# untitled.net
KiCad netlist of a schematic drawn in EAGLE
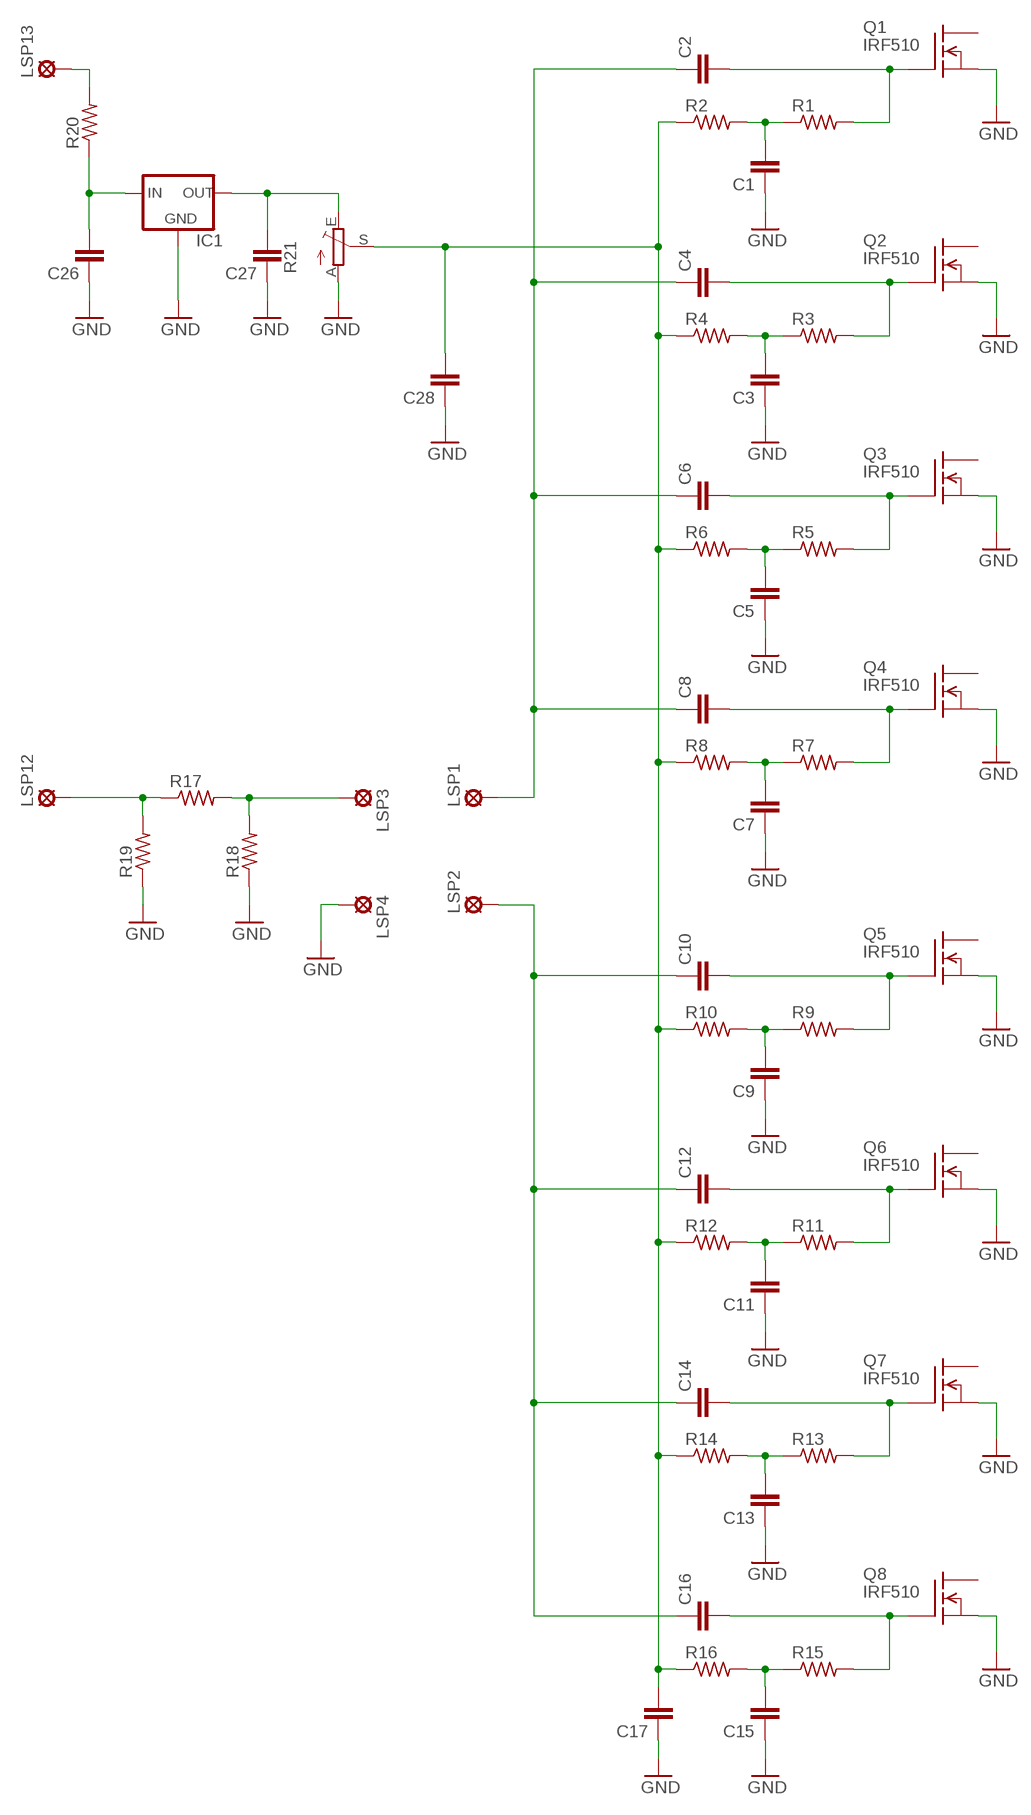
[diagram p0: schematic, sheet 1]

(export (version "E")
  (design (tool "Eeschema 10.0.6"))
  (components
    (comp (ref "C1")
      (value "C-EU075-032X103")
      (footprint "eagle-import:C075-032X103")
      (libsource (lib "eagle-import") (part "C-EU075-032X103"))
    )
    (comp (ref "C2")
      (value "C-EU075-032X103")
      (footprint "eagle-import:C075-032X103")
      (libsource (lib "eagle-import") (part "C-EU075-032X103"))
    )
    (comp (ref "C3")
      (value "C-EU075-032X103")
      (footprint "eagle-import:C075-032X103")
      (libsource (lib "eagle-import") (part "C-EU075-032X103"))
    )
    (comp (ref "C4")
      (value "C-EU075-032X103")
      (footprint "eagle-import:C075-032X103")
      (libsource (lib "eagle-import") (part "C-EU075-032X103"))
    )
    (comp (ref "C5")
      (value "C-EU075-032X103")
      (footprint "eagle-import:C075-032X103")
      (libsource (lib "eagle-import") (part "C-EU075-032X103"))
    )
    (comp (ref "C6")
      (value "C-EU075-032X103")
      (footprint "eagle-import:C075-032X103")
      (libsource (lib "eagle-import") (part "C-EU075-032X103"))
    )
    (comp (ref "C7")
      (value "C-EU075-032X103")
      (footprint "eagle-import:C075-032X103")
      (libsource (lib "eagle-import") (part "C-EU075-032X103"))
    )
    (comp (ref "C8")
      (value "C-EU075-032X103")
      (footprint "eagle-import:C075-032X103")
      (libsource (lib "eagle-import") (part "C-EU075-032X103"))
    )
    (comp (ref "C9")
      (value "C-EU075-032X103")
      (footprint "eagle-import:C075-032X103")
      (libsource (lib "eagle-import") (part "C-EU075-032X103"))
    )
    (comp (ref "C10")
      (value "C-EU075-032X103")
      (footprint "eagle-import:C075-032X103")
      (libsource (lib "eagle-import") (part "C-EU075-032X103"))
    )
    (comp (ref "C11")
      (value "C-EU075-032X103")
      (footprint "eagle-import:C075-032X103")
      (libsource (lib "eagle-import") (part "C-EU075-032X103"))
    )
    (comp (ref "C12")
      (value "C-EU075-032X103")
      (footprint "eagle-import:C075-032X103")
      (libsource (lib "eagle-import") (part "C-EU075-032X103"))
    )
    (comp (ref "C13")
      (value "C-EU075-032X103")
      (footprint "eagle-import:C075-032X103")
      (libsource (lib "eagle-import") (part "C-EU075-032X103"))
    )
    (comp (ref "C14")
      (value "C-EU075-032X103")
      (footprint "eagle-import:C075-032X103")
      (libsource (lib "eagle-import") (part "C-EU075-032X103"))
    )
    (comp (ref "C15")
      (value "C-EU075-032X103")
      (footprint "eagle-import:C075-032X103")
      (libsource (lib "eagle-import") (part "C-EU075-032X103"))
    )
    (comp (ref "C16")
      (value "C-EU075-032X103")
      (footprint "eagle-import:C075-032X103")
      (libsource (lib "eagle-import") (part "C-EU075-032X103"))
    )
    (comp (ref "C17")
      (value "C-EU075-032X103")
      (footprint "eagle-import:C075-032X103")
      (libsource (lib "eagle-import") (part "C-EU075-032X103"))
    )
    (comp (ref "C26")
      (value "C-EU075-032X103")
      (footprint "eagle-import:C075-032X103")
      (libsource (lib "eagle-import") (part "C-EU075-032X103"))
    )
    (comp (ref "C27")
      (value "C-EU075-032X103")
      (footprint "eagle-import:C075-032X103")
      (libsource (lib "eagle-import") (part "C-EU075-032X103"))
    )
    (comp (ref "C28")
      (value "C-EU075-032X103")
      (footprint "eagle-import:C075-032X103")
      (libsource (lib "eagle-import") (part "C-EU075-032X103"))
    )
    (comp (ref "IC1")
      (value "78XXS")
      (footprint "eagle-import:78XXS")
      (libsource (lib "eagle-import") (part "78XXS"))
    )
    (comp (ref "LSP1")
      (value "SE14")
      (footprint "eagle-import:SE14")
      (libsource (lib "eagle-import") (part "SE14"))
    )
    (comp (ref "LSP2")
      (value "SE14")
      (footprint "eagle-import:SE14")
      (libsource (lib "eagle-import") (part "SE14"))
    )
    (comp (ref "LSP3")
      (value "SE14")
      (footprint "eagle-import:SE14")
      (libsource (lib "eagle-import") (part "SE14"))
    )
    (comp (ref "LSP4")
      (value "SE14")
      (footprint "eagle-import:SE14")
      (libsource (lib "eagle-import") (part "SE14"))
    )
    (comp (ref "LSP12")
      (value "SE14")
      (footprint "eagle-import:SE14")
      (libsource (lib "eagle-import") (part "SE14"))
    )
    (comp (ref "LSP13")
      (value "SE14")
      (footprint "eagle-import:SE14")
      (libsource (lib "eagle-import") (part "SE14"))
    )
    (comp (ref "Q1")
      (value "IRF510")
      (footprint "eagle-import:TO220")
      (libsource (lib "eagle-import") (part "IRF510"))
    )
    (comp (ref "Q2")
      (value "IRF510")
      (footprint "eagle-import:TO220")
      (libsource (lib "eagle-import") (part "IRF510"))
    )
    (comp (ref "Q3")
      (value "IRF510")
      (footprint "eagle-import:TO220")
      (libsource (lib "eagle-import") (part "IRF510"))
    )
    (comp (ref "Q4")
      (value "IRF510")
      (footprint "eagle-import:TO220")
      (libsource (lib "eagle-import") (part "IRF510"))
    )
    (comp (ref "Q5")
      (value "IRF510")
      (footprint "eagle-import:TO220")
      (libsource (lib "eagle-import") (part "IRF510"))
    )
    (comp (ref "Q6")
      (value "IRF510")
      (footprint "eagle-import:TO220")
      (libsource (lib "eagle-import") (part "IRF510"))
    )
    (comp (ref "Q7")
      (value "IRF510")
      (footprint "eagle-import:TO220")
      (libsource (lib "eagle-import") (part "IRF510"))
    )
    (comp (ref "Q8")
      (value "IRF510")
      (footprint "eagle-import:TO220")
      (libsource (lib "eagle-import") (part "IRF510"))
    )
    (comp (ref "R1")
      (value "R-US_0309/12")
      (footprint "eagle-import:0309_12")
      (libsource (lib "eagle-import") (part "R-US_0309/12"))
    )
    (comp (ref "R2")
      (value "R-US_0309/12")
      (footprint "eagle-import:0309_12")
      (libsource (lib "eagle-import") (part "R-US_0309/12"))
    )
    (comp (ref "R3")
      (value "R-US_0309/12")
      (footprint "eagle-import:0309_12")
      (libsource (lib "eagle-import") (part "R-US_0309/12"))
    )
    (comp (ref "R4")
      (value "R-US_0309/12")
      (footprint "eagle-import:0309_12")
      (libsource (lib "eagle-import") (part "R-US_0309/12"))
    )
    (comp (ref "R5")
      (value "R-US_0309/12")
      (footprint "eagle-import:0309_12")
      (libsource (lib "eagle-import") (part "R-US_0309/12"))
    )
    (comp (ref "R6")
      (value "R-US_0309/12")
      (footprint "eagle-import:0309_12")
      (libsource (lib "eagle-import") (part "R-US_0309/12"))
    )
    (comp (ref "R7")
      (value "R-US_0309/12")
      (footprint "eagle-import:0309_12")
      (libsource (lib "eagle-import") (part "R-US_0309/12"))
    )
    (comp (ref "R8")
      (value "R-US_0309/12")
      (footprint "eagle-import:0309_12")
      (libsource (lib "eagle-import") (part "R-US_0309/12"))
    )
    (comp (ref "R9")
      (value "R-US_0309/12")
      (footprint "eagle-import:0309_12")
      (libsource (lib "eagle-import") (part "R-US_0309/12"))
    )
    (comp (ref "R10")
      (value "R-US_0309/12")
      (footprint "eagle-import:0309_12")
      (libsource (lib "eagle-import") (part "R-US_0309/12"))
    )
    (comp (ref "R11")
      (value "R-US_0309/12")
      (footprint "eagle-import:0309_12")
      (libsource (lib "eagle-import") (part "R-US_0309/12"))
    )
    (comp (ref "R12")
      (value "R-US_0309/12")
      (footprint "eagle-import:0309_12")
      (libsource (lib "eagle-import") (part "R-US_0309/12"))
    )
    (comp (ref "R13")
      (value "R-US_0309/12")
      (footprint "eagle-import:0309_12")
      (libsource (lib "eagle-import") (part "R-US_0309/12"))
    )
    (comp (ref "R14")
      (value "R-US_0309/12")
      (footprint "eagle-import:0309_12")
      (libsource (lib "eagle-import") (part "R-US_0309/12"))
    )
    (comp (ref "R15")
      (value "R-US_0309/12")
      (footprint "eagle-import:0309_12")
      (libsource (lib "eagle-import") (part "R-US_0309/12"))
    )
    (comp (ref "R16")
      (value "R-US_0309/12")
      (footprint "eagle-import:0309_12")
      (libsource (lib "eagle-import") (part "R-US_0309/12"))
    )
    (comp (ref "R17")
      (value "R-US_0309/12")
      (footprint "eagle-import:0309_12")
      (libsource (lib "eagle-import") (part "R-US_0309/12"))
    )
    (comp (ref "R18")
      (value "R-US_0309/12")
      (footprint "eagle-import:0309_12")
      (libsource (lib "eagle-import") (part "R-US_0309/12"))
    )
    (comp (ref "R19")
      (value "R-US_0309/12")
      (footprint "eagle-import:0309_12")
      (libsource (lib "eagle-import") (part "R-US_0309/12"))
    )
    (comp (ref "R20")
      (value "R-US_0309/12")
      (footprint "eagle-import:0309_12")
      (libsource (lib "eagle-import") (part "R-US_0309/12"))
    )
    (comp (ref "R21")
      (value "TRIM_EU-CA6V")
      (footprint "eagle-import:CA6V")
      (libsource (lib "eagle-import") (part "TRIM_EU-CA6V"))
    )
  )
  (nets
    (net (code "1") (name "GND") (class "Default")
      (node (ref "C1") (pin "1") (pinfunction "1_1") (pintype "passive"))
      (node (ref "C11") (pin "1") (pinfunction "1_1") (pintype "passive"))
      (node (ref "C13") (pin "1") (pinfunction "1_1") (pintype "passive"))
      (node (ref "C15") (pin "1") (pinfunction "1_1") (pintype "passive"))
      (node (ref "C17") (pin "1") (pinfunction "1_1") (pintype "passive"))
      (node (ref "C26") (pin "1") (pinfunction "1_1") (pintype "passive"))
      (node (ref "C27") (pin "1") (pinfunction "1_1") (pintype "passive"))
      (node (ref "C28") (pin "1") (pinfunction "1_1") (pintype "passive"))
      (node (ref "C3") (pin "1") (pinfunction "1_1") (pintype "passive"))
      (node (ref "C5") (pin "1") (pinfunction "1_1") (pintype "passive"))
      (node (ref "C7") (pin "1") (pinfunction "1_1") (pintype "passive"))
      (node (ref "C9") (pin "1") (pinfunction "1_1") (pintype "passive"))
      (node (ref "IC1") (pin "GND") (pinfunction "GND_GND") (pintype "input"))
      (node (ref "LSP4") (pin "MP") (pinfunction "MP_MP") (pintype "passive"))
      (node (ref "Q1") (pin "3") (pinfunction "S_3") (pintype "passive"))
      (node (ref "Q2") (pin "3") (pinfunction "S_3") (pintype "passive"))
      (node (ref "Q3") (pin "3") (pinfunction "S_3") (pintype "passive"))
      (node (ref "Q4") (pin "3") (pinfunction "S_3") (pintype "passive"))
      (node (ref "Q5") (pin "3") (pinfunction "S_3") (pintype "passive"))
      (node (ref "Q6") (pin "3") (pinfunction "S_3") (pintype "passive"))
      (node (ref "Q7") (pin "3") (pinfunction "S_3") (pintype "passive"))
      (node (ref "Q8") (pin "3") (pinfunction "S_3") (pintype "passive"))
      (node (ref "R18") (pin "1") (pinfunction "1_1") (pintype "passive"))
      (node (ref "R19") (pin "1") (pinfunction "1_1") (pintype "passive"))
      (node (ref "R21") (pin "A") (pinfunction "A_A") (pintype "passive"))
    )
    (net (code "2") (name "Net-(C1-Pad2)") (class "Default")
      (node (ref "C1") (pin "2") (pinfunction "2_2") (pintype "passive"))
      (node (ref "R1") (pin "1") (pinfunction "1_1") (pintype "passive"))
      (node (ref "R2") (pin "2") (pinfunction "2_2") (pintype "passive"))
    )
    (net (code "3") (name "Net-(C2-Pad1)") (class "Default")
      (node (ref "C2") (pin "1") (pinfunction "1_1") (pintype "passive"))
      (node (ref "C4") (pin "1") (pinfunction "1_1") (pintype "passive"))
      (node (ref "C6") (pin "1") (pinfunction "1_1") (pintype "passive"))
      (node (ref "C8") (pin "1") (pinfunction "1_1") (pintype "passive"))
      (node (ref "LSP1") (pin "MP") (pinfunction "MP_MP") (pintype "passive"))
    )
    (net (code "4") (name "Net-(C3-Pad2)") (class "Default")
      (node (ref "C3") (pin "2") (pinfunction "2_2") (pintype "passive"))
      (node (ref "R3") (pin "1") (pinfunction "1_1") (pintype "passive"))
      (node (ref "R4") (pin "2") (pinfunction "2_2") (pintype "passive"))
    )
    (net (code "5") (name "Net-(C5-Pad2)") (class "Default")
      (node (ref "C5") (pin "2") (pinfunction "2_2") (pintype "passive"))
      (node (ref "R5") (pin "1") (pinfunction "1_1") (pintype "passive"))
      (node (ref "R6") (pin "2") (pinfunction "2_2") (pintype "passive"))
    )
    (net (code "6") (name "Net-(C7-Pad2)") (class "Default")
      (node (ref "C7") (pin "2") (pinfunction "2_2") (pintype "passive"))
      (node (ref "R7") (pin "1") (pinfunction "1_1") (pintype "passive"))
      (node (ref "R8") (pin "2") (pinfunction "2_2") (pintype "passive"))
    )
    (net (code "7") (name "Net-(C9-Pad2)") (class "Default")
      (node (ref "C9") (pin "2") (pinfunction "2_2") (pintype "passive"))
      (node (ref "R10") (pin "2") (pinfunction "2_2") (pintype "passive"))
      (node (ref "R9") (pin "1") (pinfunction "1_1") (pintype "passive"))
    )
    (net (code "8") (name "Net-(C10-Pad1)") (class "Default")
      (node (ref "C10") (pin "1") (pinfunction "1_1") (pintype "passive"))
      (node (ref "C12") (pin "1") (pinfunction "1_1") (pintype "passive"))
      (node (ref "C14") (pin "1") (pinfunction "1_1") (pintype "passive"))
      (node (ref "C16") (pin "1") (pinfunction "1_1") (pintype "passive"))
      (node (ref "LSP2") (pin "MP") (pinfunction "MP_MP") (pintype "passive"))
    )
    (net (code "9") (name "Net-(C11-Pad2)") (class "Default")
      (node (ref "C11") (pin "2") (pinfunction "2_2") (pintype "passive"))
      (node (ref "R11") (pin "1") (pinfunction "1_1") (pintype "passive"))
      (node (ref "R12") (pin "2") (pinfunction "2_2") (pintype "passive"))
    )
    (net (code "10") (name "Net-(C13-Pad2)") (class "Default")
      (node (ref "C13") (pin "2") (pinfunction "2_2") (pintype "passive"))
      (node (ref "R13") (pin "1") (pinfunction "1_1") (pintype "passive"))
      (node (ref "R14") (pin "2") (pinfunction "2_2") (pintype "passive"))
    )
    (net (code "11") (name "Net-(C15-Pad2)") (class "Default")
      (node (ref "C15") (pin "2") (pinfunction "2_2") (pintype "passive"))
      (node (ref "R15") (pin "1") (pinfunction "1_1") (pintype "passive"))
      (node (ref "R16") (pin "2") (pinfunction "2_2") (pintype "passive"))
    )
    (net (code "12") (name "Net-(C17-Pad2)") (class "Default")
      (node (ref "C17") (pin "2") (pinfunction "2_2") (pintype "passive"))
      (node (ref "C28") (pin "2") (pinfunction "2_2") (pintype "passive"))
      (node (ref "R10") (pin "1") (pinfunction "1_1") (pintype "passive"))
      (node (ref "R12") (pin "1") (pinfunction "1_1") (pintype "passive"))
      (node (ref "R14") (pin "1") (pinfunction "1_1") (pintype "passive"))
      (node (ref "R16") (pin "1") (pinfunction "1_1") (pintype "passive"))
      (node (ref "R2") (pin "1") (pinfunction "1_1") (pintype "passive"))
      (node (ref "R21") (pin "S") (pinfunction "S_S") (pintype "passive"))
      (node (ref "R4") (pin "1") (pinfunction "1_1") (pintype "passive"))
      (node (ref "R6") (pin "1") (pinfunction "1_1") (pintype "passive"))
      (node (ref "R8") (pin "1") (pinfunction "1_1") (pintype "passive"))
    )
    (net (code "13") (name "Net-(C26-Pad2)") (class "Default")
      (node (ref "C26") (pin "2") (pinfunction "2_2") (pintype "passive"))
      (node (ref "IC1") (pin "IN") (pinfunction "IN_IN") (pintype "input"))
      (node (ref "R20") (pin "1") (pinfunction "1_1") (pintype "passive"))
    )
    (net (code "14") (name "Net-(C27-Pad2)") (class "Default")
      (node (ref "C27") (pin "2") (pinfunction "2_2") (pintype "passive"))
      (node (ref "IC1") (pin "OUT") (pinfunction "OUT_OUT") (pintype "passive"))
      (node (ref "R21") (pin "E") (pinfunction "E_E") (pintype "passive"))
    )
    (net (code "15") (name "Net-(LSP3-PadMP)") (class "Default")
      (node (ref "LSP3") (pin "MP") (pinfunction "MP_MP") (pintype "passive"))
      (node (ref "R17") (pin "2") (pinfunction "2_2") (pintype "passive"))
      (node (ref "R18") (pin "2") (pinfunction "2_2") (pintype "passive"))
    )
    (net (code "16") (name "Net-(LSP12-PadMP)") (class "Default")
      (node (ref "LSP12") (pin "MP") (pinfunction "MP_MP") (pintype "passive"))
      (node (ref "R17") (pin "1") (pinfunction "1_1") (pintype "passive"))
      (node (ref "R19") (pin "2") (pinfunction "2_2") (pintype "passive"))
    )
    (net (code "17") (name "Net-(LSP13-PadMP)") (class "Default")
      (node (ref "LSP13") (pin "MP") (pinfunction "MP_MP") (pintype "passive"))
      (node (ref "R20") (pin "2") (pinfunction "2_2") (pintype "passive"))
    )
    (net (code "18") (name "Net-(Q1-G)") (class "Default")
      (node (ref "C2") (pin "2") (pinfunction "2_2") (pintype "passive"))
      (node (ref "Q1") (pin "1") (pinfunction "G_1") (pintype "passive"))
      (node (ref "R1") (pin "2") (pinfunction "2_2") (pintype "passive"))
    )
    (net (code "19") (name "Net-(Q2-G)") (class "Default")
      (node (ref "C4") (pin "2") (pinfunction "2_2") (pintype "passive"))
      (node (ref "Q2") (pin "1") (pinfunction "G_1") (pintype "passive"))
      (node (ref "R3") (pin "2") (pinfunction "2_2") (pintype "passive"))
    )
    (net (code "20") (name "Net-(Q3-G)") (class "Default")
      (node (ref "C6") (pin "2") (pinfunction "2_2") (pintype "passive"))
      (node (ref "Q3") (pin "1") (pinfunction "G_1") (pintype "passive"))
      (node (ref "R5") (pin "2") (pinfunction "2_2") (pintype "passive"))
    )
    (net (code "21") (name "Net-(Q4-G)") (class "Default")
      (node (ref "C8") (pin "2") (pinfunction "2_2") (pintype "passive"))
      (node (ref "Q4") (pin "1") (pinfunction "G_1") (pintype "passive"))
      (node (ref "R7") (pin "2") (pinfunction "2_2") (pintype "passive"))
    )
    (net (code "22") (name "Net-(Q5-G)") (class "Default")
      (node (ref "C10") (pin "2") (pinfunction "2_2") (pintype "passive"))
      (node (ref "Q5") (pin "1") (pinfunction "G_1") (pintype "passive"))
      (node (ref "R9") (pin "2") (pinfunction "2_2") (pintype "passive"))
    )
    (net (code "23") (name "Net-(Q6-G)") (class "Default")
      (node (ref "C12") (pin "2") (pinfunction "2_2") (pintype "passive"))
      (node (ref "Q6") (pin "1") (pinfunction "G_1") (pintype "passive"))
      (node (ref "R11") (pin "2") (pinfunction "2_2") (pintype "passive"))
    )
    (net (code "24") (name "Net-(Q7-G)") (class "Default")
      (node (ref "C14") (pin "2") (pinfunction "2_2") (pintype "passive"))
      (node (ref "Q7") (pin "1") (pinfunction "G_1") (pintype "passive"))
      (node (ref "R13") (pin "2") (pinfunction "2_2") (pintype "passive"))
    )
    (net (code "25") (name "Net-(Q8-G)") (class "Default")
      (node (ref "C16") (pin "2") (pinfunction "2_2") (pintype "passive"))
      (node (ref "Q8") (pin "1") (pinfunction "G_1") (pintype "passive"))
      (node (ref "R15") (pin "2") (pinfunction "2_2") (pintype "passive"))
    )
    (net (code "26") (name "unconnected-(Q1-D-Pad2)") (class "Default")
      (node (ref "Q1") (pin "2") (pinfunction "D_2") (pintype "passive"))
    )
    (net (code "27") (name "unconnected-(Q2-D-Pad2)") (class "Default")
      (node (ref "Q2") (pin "2") (pinfunction "D_2") (pintype "passive"))
    )
    (net (code "28") (name "unconnected-(Q3-D-Pad2)") (class "Default")
      (node (ref "Q3") (pin "2") (pinfunction "D_2") (pintype "passive"))
    )
    (net (code "29") (name "unconnected-(Q4-D-Pad2)") (class "Default")
      (node (ref "Q4") (pin "2") (pinfunction "D_2") (pintype "passive"))
    )
    (net (code "30") (name "unconnected-(Q5-D-Pad2)") (class "Default")
      (node (ref "Q5") (pin "2") (pinfunction "D_2") (pintype "passive"))
    )
    (net (code "31") (name "unconnected-(Q6-D-Pad2)") (class "Default")
      (node (ref "Q6") (pin "2") (pinfunction "D_2") (pintype "passive"))
    )
    (net (code "32") (name "unconnected-(Q7-D-Pad2)") (class "Default")
      (node (ref "Q7") (pin "2") (pinfunction "D_2") (pintype "passive"))
    )
    (net (code "33") (name "unconnected-(Q8-D-Pad2)") (class "Default")
      (node (ref "Q8") (pin "2") (pinfunction "D_2") (pintype "passive"))
    )
  )
)
